# 2_cyber60-mx-matrix.net
KiCad netlist of a schematic drawn in Altium Designer
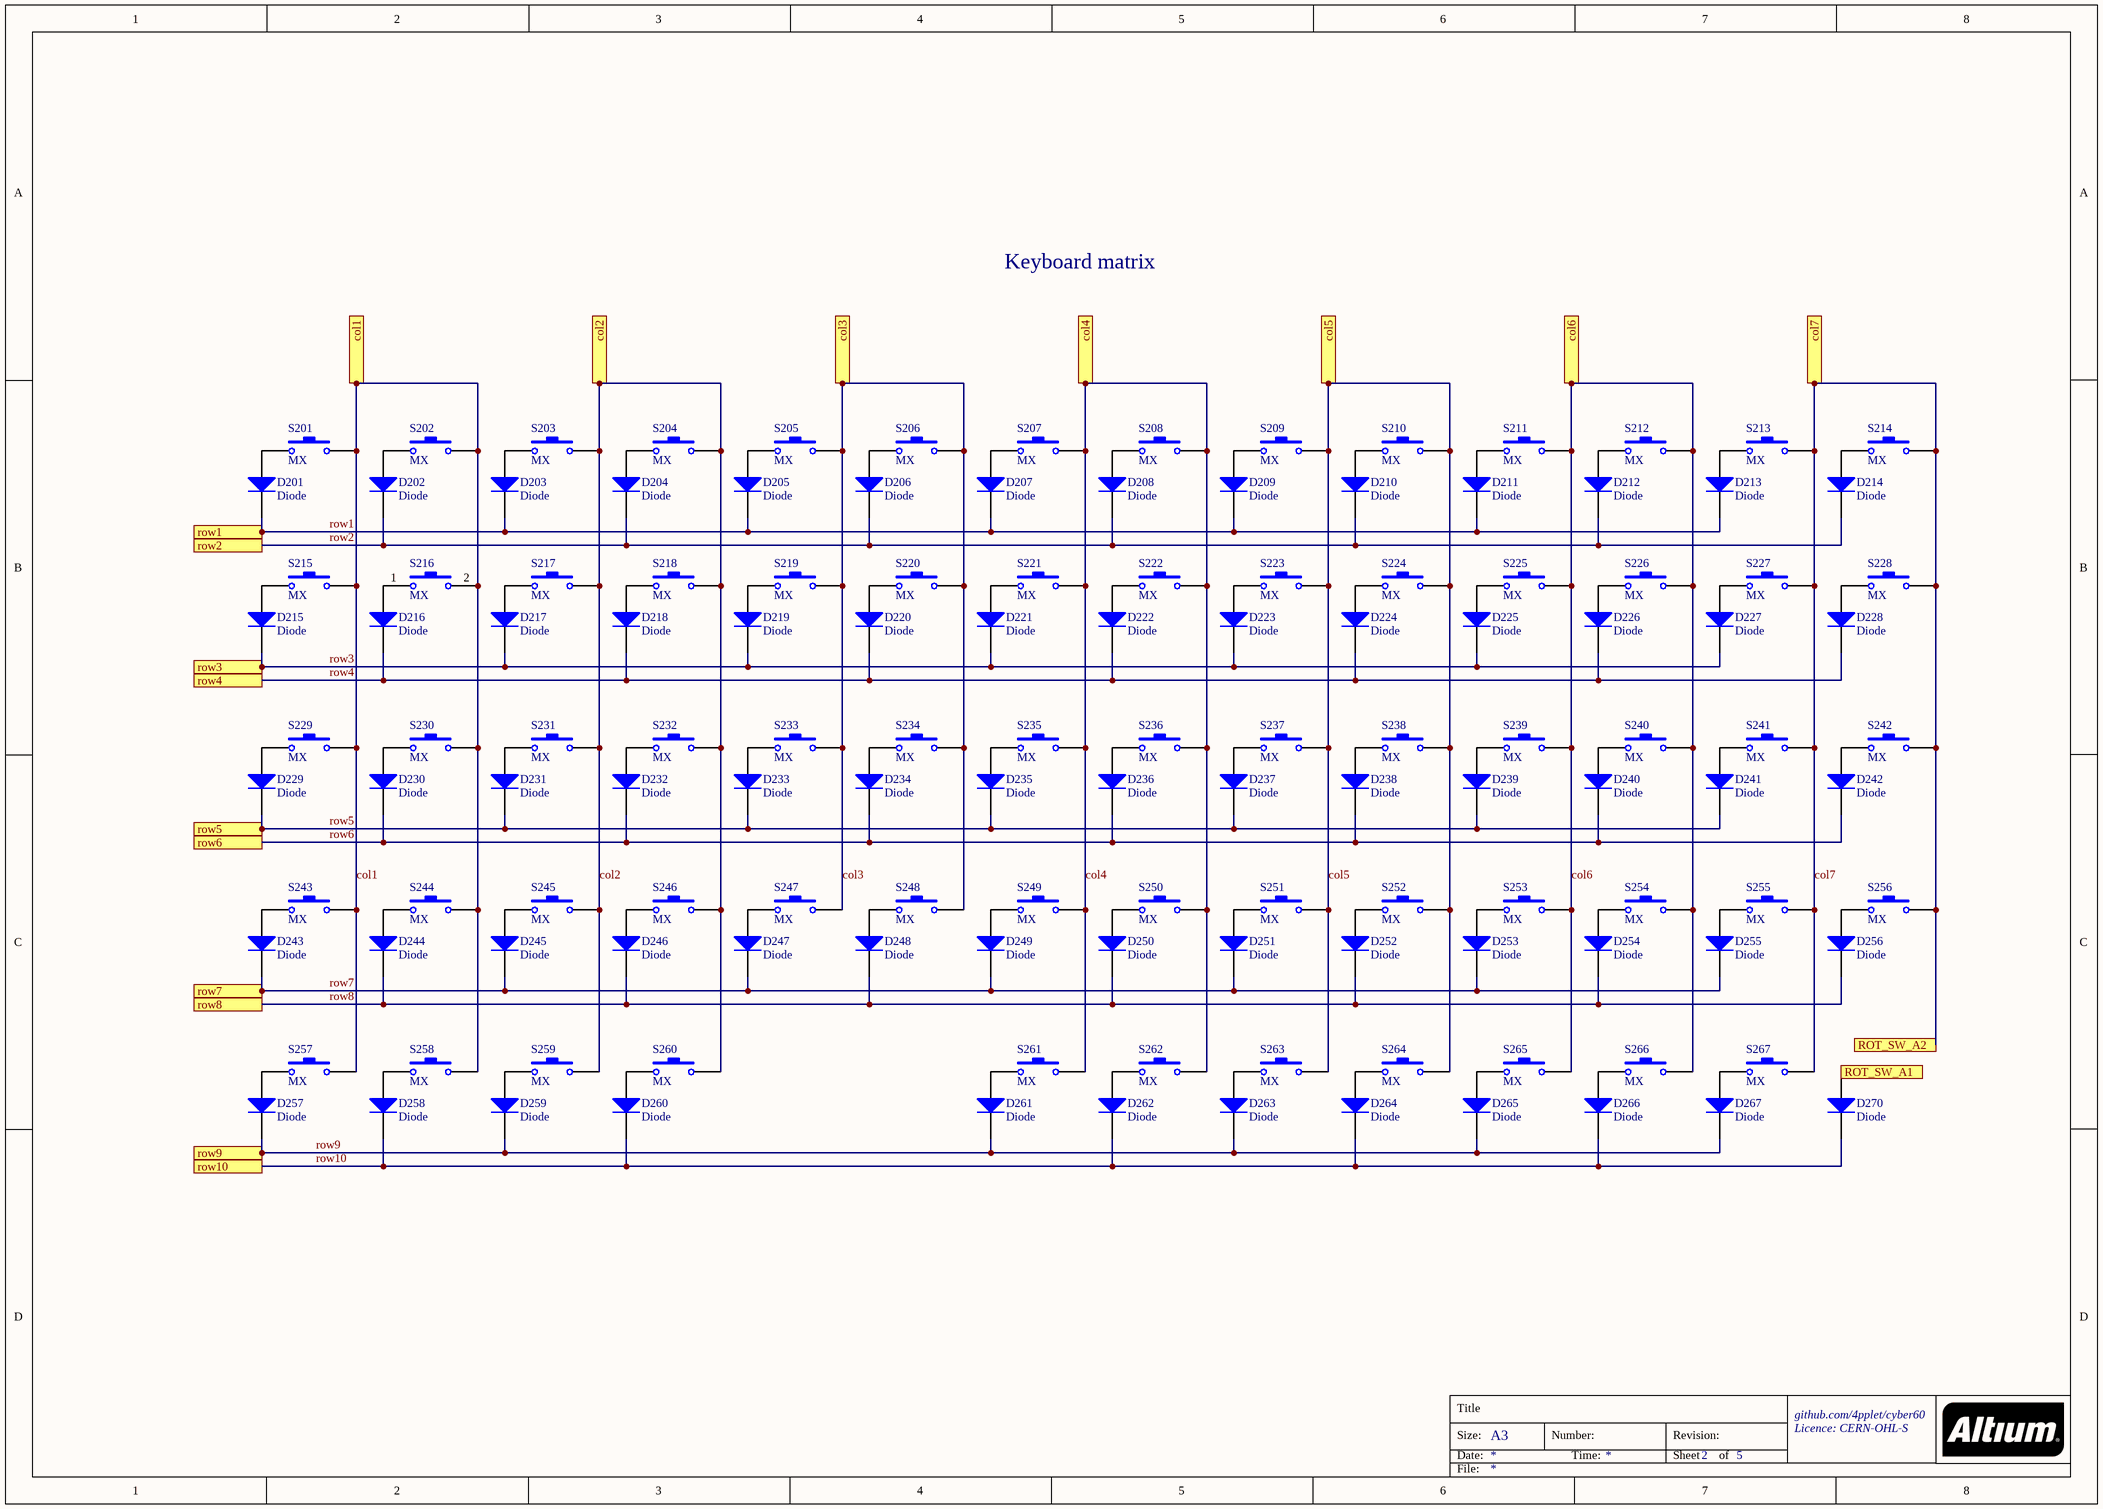
[diagram p0: 2_cyber60-mx-matrix.SchDoc]

(export (version "E")
  (design (tool "Eeschema 10.0.6"))
  (components
    (comp (ref "D201")
      (value "Diode")
      (footprint "SOD-123")
      (description "Default Diode")
      (fields (field (name "LCSC PART #") "C81598") (field (name "MRF.PART") "1N4148W"))
      (libsource (lib "Miscellaneous Devices") (part "Diode"))
    )
    (comp (ref "D202")
      (value "Diode")
      (footprint "SOD-123")
      (description "Default Diode")
      (fields (field (name "LCSC PART #") "C81598") (field (name "MRF.PART") "1N4148W"))
      (libsource (lib "Miscellaneous Devices") (part "Diode"))
    )
    (comp (ref "D203")
      (value "Diode")
      (footprint "SOD-123")
      (description "Default Diode")
      (fields (field (name "LCSC PART #") "C81598") (field (name "MRF.PART") "1N4148W"))
      (libsource (lib "Miscellaneous Devices") (part "Diode"))
    )
    (comp (ref "D204")
      (value "Diode")
      (footprint "SOD-123")
      (description "Default Diode")
      (fields (field (name "LCSC PART #") "C81598") (field (name "MRF.PART") "1N4148W"))
      (libsource (lib "Miscellaneous Devices") (part "Diode"))
    )
    (comp (ref "D205")
      (value "Diode")
      (footprint "SOD-123")
      (description "Default Diode")
      (fields (field (name "LCSC PART #") "C81598") (field (name "MRF.PART") "1N4148W"))
      (libsource (lib "Miscellaneous Devices") (part "Diode"))
    )
    (comp (ref "D206")
      (value "Diode")
      (footprint "SOD-123")
      (description "Default Diode")
      (fields (field (name "LCSC PART #") "C81598") (field (name "MRF.PART") "1N4148W"))
      (libsource (lib "Miscellaneous Devices") (part "Diode"))
    )
    (comp (ref "D207")
      (value "Diode")
      (footprint "SOD-123")
      (description "Default Diode")
      (fields (field (name "LCSC PART #") "C81598") (field (name "MRF.PART") "1N4148W"))
      (libsource (lib "Miscellaneous Devices") (part "Diode"))
    )
    (comp (ref "D208")
      (value "Diode")
      (footprint "SOD-123")
      (description "Default Diode")
      (fields (field (name "LCSC PART #") "C81598") (field (name "MRF.PART") "1N4148W"))
      (libsource (lib "Miscellaneous Devices") (part "Diode"))
    )
    (comp (ref "D209")
      (value "Diode")
      (footprint "SOD-123")
      (description "Default Diode")
      (fields (field (name "LCSC PART #") "C81598") (field (name "MRF.PART") "1N4148W"))
      (libsource (lib "Miscellaneous Devices") (part "Diode"))
    )
    (comp (ref "D210")
      (value "Diode")
      (footprint "SOD-123")
      (description "Default Diode")
      (fields (field (name "LCSC PART #") "C81598") (field (name "MRF.PART") "1N4148W"))
      (libsource (lib "Miscellaneous Devices") (part "Diode"))
    )
    (comp (ref "D211")
      (value "Diode")
      (footprint "SOD-123")
      (description "Default Diode")
      (fields (field (name "LCSC PART #") "C81598") (field (name "MRF.PART") "1N4148W"))
      (libsource (lib "Miscellaneous Devices") (part "Diode"))
    )
    (comp (ref "D212")
      (value "Diode")
      (footprint "SOD-123")
      (description "Default Diode")
      (fields (field (name "LCSC PART #") "C81598") (field (name "MRF.PART") "1N4148W"))
      (libsource (lib "Miscellaneous Devices") (part "Diode"))
    )
    (comp (ref "D213")
      (value "Diode")
      (footprint "SOD-123")
      (description "Default Diode")
      (fields (field (name "LCSC PART #") "C81598") (field (name "MRF.PART") "1N4148W"))
      (libsource (lib "Miscellaneous Devices") (part "Diode"))
    )
    (comp (ref "D214")
      (value "Diode")
      (footprint "SOD-123")
      (description "Default Diode")
      (fields (field (name "LCSC PART #") "C81598") (field (name "MRF.PART") "1N4148W"))
      (libsource (lib "Miscellaneous Devices") (part "Diode"))
    )
    (comp (ref "D215")
      (value "Diode")
      (footprint "SOD-123")
      (description "Default Diode")
      (fields (field (name "LCSC PART #") "C81598") (field (name "MRF.PART") "1N4148W"))
      (libsource (lib "Miscellaneous Devices") (part "Diode"))
    )
    (comp (ref "D216")
      (value "Diode")
      (footprint "SOD-123")
      (description "Default Diode")
      (fields (field (name "LCSC PART #") "C81598") (field (name "MRF.PART") "1N4148W"))
      (libsource (lib "Miscellaneous Devices") (part "Diode"))
    )
    (comp (ref "D217")
      (value "Diode")
      (footprint "SOD-123")
      (description "Default Diode")
      (fields (field (name "LCSC PART #") "C81598") (field (name "MRF.PART") "1N4148W"))
      (libsource (lib "Miscellaneous Devices") (part "Diode"))
    )
    (comp (ref "D218")
      (value "Diode")
      (footprint "SOD-123")
      (description "Default Diode")
      (fields (field (name "LCSC PART #") "C81598") (field (name "MRF.PART") "1N4148W"))
      (libsource (lib "Miscellaneous Devices") (part "Diode"))
    )
    (comp (ref "D219")
      (value "Diode")
      (footprint "SOD-123")
      (description "Default Diode")
      (fields (field (name "LCSC PART #") "C81598") (field (name "MRF.PART") "1N4148W"))
      (libsource (lib "Miscellaneous Devices") (part "Diode"))
    )
    (comp (ref "D220")
      (value "Diode")
      (footprint "SOD-123")
      (description "Default Diode")
      (fields (field (name "LCSC PART #") "C81598") (field (name "MRF.PART") "1N4148W"))
      (libsource (lib "Miscellaneous Devices") (part "Diode"))
    )
    (comp (ref "D221")
      (value "Diode")
      (footprint "SOD-123")
      (description "Default Diode")
      (fields (field (name "LCSC PART #") "C81598") (field (name "MRF.PART") "1N4148W"))
      (libsource (lib "Miscellaneous Devices") (part "Diode"))
    )
    (comp (ref "D222")
      (value "Diode")
      (footprint "SOD-123")
      (description "Default Diode")
      (fields (field (name "LCSC PART #") "C81598") (field (name "MRF.PART") "1N4148W"))
      (libsource (lib "Miscellaneous Devices") (part "Diode"))
    )
    (comp (ref "D223")
      (value "Diode")
      (footprint "SOD-123")
      (description "Default Diode")
      (fields (field (name "LCSC PART #") "C81598") (field (name "MRF.PART") "1N4148W"))
      (libsource (lib "Miscellaneous Devices") (part "Diode"))
    )
    (comp (ref "D224")
      (value "Diode")
      (footprint "SOD-123")
      (description "Default Diode")
      (fields (field (name "LCSC PART #") "C81598") (field (name "MRF.PART") "1N4148W"))
      (libsource (lib "Miscellaneous Devices") (part "Diode"))
    )
    (comp (ref "D225")
      (value "Diode")
      (footprint "SOD-123")
      (description "Default Diode")
      (fields (field (name "LCSC PART #") "C81598") (field (name "MRF.PART") "1N4148W"))
      (libsource (lib "Miscellaneous Devices") (part "Diode"))
    )
    (comp (ref "D226")
      (value "Diode")
      (footprint "SOD-123")
      (description "Default Diode")
      (fields (field (name "LCSC PART #") "C81598") (field (name "MRF.PART") "1N4148W"))
      (libsource (lib "Miscellaneous Devices") (part "Diode"))
    )
    (comp (ref "D227")
      (value "Diode")
      (footprint "SOD-123")
      (description "Default Diode")
      (fields (field (name "LCSC PART #") "C81598") (field (name "MRF.PART") "1N4148W"))
      (libsource (lib "Miscellaneous Devices") (part "Diode"))
    )
    (comp (ref "D228")
      (value "Diode")
      (footprint "SOD-123")
      (description "Default Diode")
      (fields (field (name "LCSC PART #") "C81598") (field (name "MRF.PART") "1N4148W"))
      (libsource (lib "Miscellaneous Devices") (part "Diode"))
    )
    (comp (ref "D229")
      (value "Diode")
      (footprint "SOD-123")
      (description "Default Diode")
      (fields (field (name "LCSC PART #") "C81598") (field (name "MRF.PART") "1N4148W"))
      (libsource (lib "Miscellaneous Devices") (part "Diode"))
    )
    (comp (ref "D230")
      (value "Diode")
      (footprint "SOD-123")
      (description "Default Diode")
      (fields (field (name "LCSC PART #") "C81598") (field (name "MRF.PART") "1N4148W"))
      (libsource (lib "Miscellaneous Devices") (part "Diode"))
    )
    (comp (ref "D231")
      (value "Diode")
      (footprint "SOD-123")
      (description "Default Diode")
      (fields (field (name "LCSC PART #") "C81598") (field (name "MRF.PART") "1N4148W"))
      (libsource (lib "Miscellaneous Devices") (part "Diode"))
    )
    (comp (ref "D232")
      (value "Diode")
      (footprint "SOD-123")
      (description "Default Diode")
      (fields (field (name "LCSC PART #") "C81598") (field (name "MRF.PART") "1N4148W"))
      (libsource (lib "Miscellaneous Devices") (part "Diode"))
    )
    (comp (ref "D233")
      (value "Diode")
      (footprint "SOD-123")
      (description "Default Diode")
      (fields (field (name "LCSC PART #") "C81598") (field (name "MRF.PART") "1N4148W"))
      (libsource (lib "Miscellaneous Devices") (part "Diode"))
    )
    (comp (ref "D234")
      (value "Diode")
      (footprint "SOD-123")
      (description "Default Diode")
      (fields (field (name "LCSC PART #") "C81598") (field (name "MRF.PART") "1N4148W"))
      (libsource (lib "Miscellaneous Devices") (part "Diode"))
    )
    (comp (ref "D235")
      (value "Diode")
      (footprint "SOD-123")
      (description "Default Diode")
      (fields (field (name "LCSC PART #") "C81598") (field (name "MRF.PART") "1N4148W"))
      (libsource (lib "Miscellaneous Devices") (part "Diode"))
    )
    (comp (ref "D236")
      (value "Diode")
      (footprint "SOD-123")
      (description "Default Diode")
      (fields (field (name "LCSC PART #") "C81598") (field (name "MRF.PART") "1N4148W"))
      (libsource (lib "Miscellaneous Devices") (part "Diode"))
    )
    (comp (ref "D237")
      (value "Diode")
      (footprint "SOD-123")
      (description "Default Diode")
      (fields (field (name "LCSC PART #") "C81598") (field (name "MRF.PART") "1N4148W"))
      (libsource (lib "Miscellaneous Devices") (part "Diode"))
    )
    (comp (ref "D238")
      (value "Diode")
      (footprint "SOD-123")
      (description "Default Diode")
      (fields (field (name "LCSC PART #") "C81598") (field (name "MRF.PART") "1N4148W"))
      (libsource (lib "Miscellaneous Devices") (part "Diode"))
    )
    (comp (ref "D239")
      (value "Diode")
      (footprint "SOD-123")
      (description "Default Diode")
      (fields (field (name "LCSC PART #") "C81598") (field (name "MRF.PART") "1N4148W"))
      (libsource (lib "Miscellaneous Devices") (part "Diode"))
    )
    (comp (ref "D240")
      (value "Diode")
      (footprint "SOD-123")
      (description "Default Diode")
      (fields (field (name "LCSC PART #") "C81598") (field (name "MRF.PART") "1N4148W"))
      (libsource (lib "Miscellaneous Devices") (part "Diode"))
    )
    (comp (ref "D241")
      (value "Diode")
      (footprint "SOD-123")
      (description "Default Diode")
      (fields (field (name "LCSC PART #") "C81598") (field (name "MRF.PART") "1N4148W"))
      (libsource (lib "Miscellaneous Devices") (part "Diode"))
    )
    (comp (ref "D242")
      (value "Diode")
      (footprint "SOD-123")
      (description "Default Diode")
      (fields (field (name "LCSC PART #") "C81598") (field (name "MRF.PART") "1N4148W"))
      (libsource (lib "Miscellaneous Devices") (part "Diode"))
    )
    (comp (ref "D243")
      (value "Diode")
      (footprint "SOD-123")
      (description "Default Diode")
      (fields (field (name "LCSC PART #") "C81598") (field (name "MRF.PART") "1N4148W"))
      (libsource (lib "Miscellaneous Devices") (part "Diode"))
    )
    (comp (ref "D244")
      (value "Diode")
      (footprint "SOD-123")
      (description "Default Diode")
      (fields (field (name "LCSC PART #") "C81598") (field (name "MRF.PART") "1N4148W"))
      (libsource (lib "Miscellaneous Devices") (part "Diode"))
    )
    (comp (ref "D245")
      (value "Diode")
      (footprint "SOD-123")
      (description "Default Diode")
      (fields (field (name "LCSC PART #") "C81598") (field (name "MRF.PART") "1N4148W"))
      (libsource (lib "Miscellaneous Devices") (part "Diode"))
    )
    (comp (ref "D246")
      (value "Diode")
      (footprint "SOD-123")
      (description "Default Diode")
      (fields (field (name "LCSC PART #") "C81598") (field (name "MRF.PART") "1N4148W"))
      (libsource (lib "Miscellaneous Devices") (part "Diode"))
    )
    (comp (ref "D247")
      (value "Diode")
      (footprint "SOD-123")
      (description "Default Diode")
      (fields (field (name "LCSC PART #") "C81598") (field (name "MRF.PART") "1N4148W"))
      (libsource (lib "Miscellaneous Devices") (part "Diode"))
    )
    (comp (ref "D248")
      (value "Diode")
      (footprint "SOD-123")
      (description "Default Diode")
      (fields (field (name "LCSC PART #") "C81598") (field (name "MRF.PART") "1N4148W"))
      (libsource (lib "Miscellaneous Devices") (part "Diode"))
    )
    (comp (ref "D249")
      (value "Diode")
      (footprint "SOD-123")
      (description "Default Diode")
      (fields (field (name "LCSC PART #") "C81598") (field (name "MRF.PART") "1N4148W"))
      (libsource (lib "Miscellaneous Devices") (part "Diode"))
    )
    (comp (ref "D250")
      (value "Diode")
      (footprint "SOD-123")
      (description "Default Diode")
      (fields (field (name "LCSC PART #") "C81598") (field (name "MRF.PART") "1N4148W"))
      (libsource (lib "Miscellaneous Devices") (part "Diode"))
    )
    (comp (ref "D251")
      (value "Diode")
      (footprint "SOD-123")
      (description "Default Diode")
      (fields (field (name "LCSC PART #") "C81598") (field (name "MRF.PART") "1N4148W"))
      (libsource (lib "Miscellaneous Devices") (part "Diode"))
    )
    (comp (ref "D252")
      (value "Diode")
      (footprint "SOD-123")
      (description "Default Diode")
      (fields (field (name "LCSC PART #") "C81598") (field (name "MRF.PART") "1N4148W"))
      (libsource (lib "Miscellaneous Devices") (part "Diode"))
    )
    (comp (ref "D253")
      (value "Diode")
      (footprint "SOD-123")
      (description "Default Diode")
      (fields (field (name "LCSC PART #") "C81598") (field (name "MRF.PART") "1N4148W"))
      (libsource (lib "Miscellaneous Devices") (part "Diode"))
    )
    (comp (ref "D254")
      (value "Diode")
      (footprint "SOD-123")
      (description "Default Diode")
      (fields (field (name "LCSC PART #") "C81598") (field (name "MRF.PART") "1N4148W"))
      (libsource (lib "Miscellaneous Devices") (part "Diode"))
    )
    (comp (ref "D255")
      (value "Diode")
      (footprint "SOD-123")
      (description "Default Diode")
      (fields (field (name "LCSC PART #") "C81598") (field (name "MRF.PART") "1N4148W"))
      (libsource (lib "Miscellaneous Devices") (part "Diode"))
    )
    (comp (ref "D256")
      (value "Diode")
      (footprint "SOD-123")
      (description "Default Diode")
      (fields (field (name "LCSC PART #") "C81598") (field (name "MRF.PART") "1N4148W"))
      (libsource (lib "Miscellaneous Devices") (part "Diode"))
    )
    (comp (ref "D257")
      (value "Diode")
      (footprint "SOD-123")
      (description "Default Diode")
      (fields (field (name "LCSC PART #") "C81598") (field (name "MRF.PART") "1N4148W"))
      (libsource (lib "Miscellaneous Devices") (part "Diode"))
    )
    (comp (ref "D258")
      (value "Diode")
      (footprint "SOD-123")
      (description "Default Diode")
      (fields (field (name "LCSC PART #") "C81598") (field (name "MRF.PART") "1N4148W"))
      (libsource (lib "Miscellaneous Devices") (part "Diode"))
    )
    (comp (ref "D259")
      (value "Diode")
      (footprint "SOD-123")
      (description "Default Diode")
      (fields (field (name "LCSC PART #") "C81598") (field (name "MRF.PART") "1N4148W"))
      (libsource (lib "Miscellaneous Devices") (part "Diode"))
    )
    (comp (ref "D260")
      (value "Diode")
      (footprint "SOD-123")
      (description "Default Diode")
      (fields (field (name "LCSC PART #") "C81598") (field (name "MRF.PART") "1N4148W"))
      (libsource (lib "Miscellaneous Devices") (part "Diode"))
    )
    (comp (ref "D261")
      (value "Diode")
      (footprint "SOD-123")
      (description "Default Diode")
      (fields (field (name "LCSC PART #") "C81598") (field (name "MRF.PART") "1N4148W"))
      (libsource (lib "Miscellaneous Devices") (part "Diode"))
    )
    (comp (ref "D262")
      (value "Diode")
      (footprint "SOD-123")
      (description "Default Diode")
      (fields (field (name "LCSC PART #") "C81598") (field (name "MRF.PART") "1N4148W"))
      (libsource (lib "Miscellaneous Devices") (part "Diode"))
    )
    (comp (ref "D263")
      (value "Diode")
      (footprint "SOD-123")
      (description "Default Diode")
      (fields (field (name "LCSC PART #") "C81598") (field (name "MRF.PART") "1N4148W"))
      (libsource (lib "Miscellaneous Devices") (part "Diode"))
    )
    (comp (ref "D264")
      (value "Diode")
      (footprint "SOD-123")
      (description "Default Diode")
      (fields (field (name "LCSC PART #") "C81598") (field (name "MRF.PART") "1N4148W"))
      (libsource (lib "Miscellaneous Devices") (part "Diode"))
    )
    (comp (ref "D265")
      (value "Diode")
      (footprint "SOD-123")
      (description "Default Diode")
      (fields (field (name "LCSC PART #") "C81598") (field (name "MRF.PART") "1N4148W"))
      (libsource (lib "Miscellaneous Devices") (part "Diode"))
    )
    (comp (ref "D266")
      (value "Diode")
      (footprint "SOD-123")
      (description "Default Diode")
      (fields (field (name "LCSC PART #") "C81598") (field (name "MRF.PART") "1N4148W"))
      (libsource (lib "Miscellaneous Devices") (part "Diode"))
    )
    (comp (ref "D267")
      (value "Diode")
      (footprint "SOD-123")
      (description "Default Diode")
      (fields (field (name "LCSC PART #") "C81598") (field (name "MRF.PART") "1N4148W"))
      (libsource (lib "Miscellaneous Devices") (part "Diode"))
    )
    (comp (ref "D270")
      (value "Diode")
      (footprint "SOD-123")
      (description "Default Diode")
      (fields (field (name "LCSC PART #") "C81598") (field (name "MRF.PART") "1N4148W"))
      (libsource (lib "Miscellaneous Devices") (part "Diode"))
    )
    (comp (ref "S201")
      (value "MX")
      (footprint "MX-switch - switched pol")
      (description "Switch")
      (libsource (lib "Miscellaneous Devices") (part "SW-PB"))
    )
    (comp (ref "S202")
      (value "MX")
      (footprint "MX-switch - switched pol - connector")
      (description "Switch")
      (libsource (lib "Miscellaneous Devices") (part "SW-PB"))
    )
    (comp (ref "S203")
      (value "MX")
      (footprint "MX-switch - switched pol")
      (description "Switch")
      (libsource (lib "Miscellaneous Devices") (part "SW-PB"))
    )
    (comp (ref "S204")
      (value "MX")
      (footprint "MX-switch")
      (description "Switch")
      (libsource (lib "Miscellaneous Devices") (part "SW-PB"))
    )
    (comp (ref "S205")
      (value "MX")
      (footprint "MX-switch - switched pol")
      (description "Switch")
      (libsource (lib "Miscellaneous Devices") (part "SW-PB"))
    )
    (comp (ref "S206")
      (value "MX")
      (footprint "MX-switch - switched pol")
      (description "Switch")
      (libsource (lib "Miscellaneous Devices") (part "SW-PB"))
    )
    (comp (ref "S207")
      (value "MX")
      (footprint "MX-switch - switched pol")
      (description "Switch")
      (libsource (lib "Miscellaneous Devices") (part "SW-PB"))
    )
    (comp (ref "S208")
      (value "MX")
      (footprint "MX-switch - switched pol")
      (description "Switch")
      (libsource (lib "Miscellaneous Devices") (part "SW-PB"))
    )
    (comp (ref "S209")
      (value "MX")
      (footprint "MX-switch - switched pol")
      (description "Switch")
      (libsource (lib "Miscellaneous Devices") (part "SW-PB"))
    )
    (comp (ref "S210")
      (value "MX")
      (footprint "MX-switch - switched pol")
      (description "Switch")
      (libsource (lib "Miscellaneous Devices") (part "SW-PB"))
    )
    (comp (ref "S211")
      (value "MX")
      (footprint "MX-switch - switched pol")
      (description "Switch")
      (libsource (lib "Miscellaneous Devices") (part "SW-PB"))
    )
    (comp (ref "S212")
      (value "MX")
      (footprint "MX-switch - switched pol")
      (description "Switch")
      (libsource (lib "Miscellaneous Devices") (part "SW-PB"))
    )
    (comp (ref "S213")
      (value "MX")
      (footprint "MX-switch - switched pol")
      (description "Switch")
      (libsource (lib "Miscellaneous Devices") (part "SW-PB"))
    )
    (comp (ref "S214")
      (value "MX")
      (footprint "MX-switch - switched pol")
      (description "Switch")
      (libsource (lib "Miscellaneous Devices") (part "SW-PB"))
    )
    (comp (ref "S215")
      (value "MX")
      (footprint "MX-switch - 1.5U - switched pol")
      (description "TAB")
      (libsource (lib "Miscellaneous Devices") (part "SW-PB"))
    )
    (comp (ref "S216")
      (value "MX")
      (footprint "MX-switch - switched pol")
      (description "Switch")
      (libsource (lib "") (part "SW-PB_1"))
    )
    (comp (ref "S217")
      (value "MX")
      (footprint "MX-switch - switched pol")
      (description "Switch")
      (libsource (lib "Miscellaneous Devices") (part "SW-PB"))
    )
    (comp (ref "S218")
      (value "MX")
      (footprint "MX-switch - switched pol")
      (description "Switch")
      (libsource (lib "Miscellaneous Devices") (part "SW-PB"))
    )
    (comp (ref "S219")
      (value "MX")
      (footprint "MX-switch - switched pol")
      (description "Switch")
      (libsource (lib "Miscellaneous Devices") (part "SW-PB"))
    )
    (comp (ref "S220")
      (value "MX")
      (footprint "MX-switch")
      (description "Switch")
      (libsource (lib "Miscellaneous Devices") (part "SW-PB"))
    )
    (comp (ref "S221")
      (value "MX")
      (footprint "MX-switch - switched pol")
      (description "Switch")
      (libsource (lib "Miscellaneous Devices") (part "SW-PB"))
    )
    (comp (ref "S222")
      (value "MX")
      (footprint "MX-switch - switched pol")
      (description "Switch")
      (libsource (lib "Miscellaneous Devices") (part "SW-PB"))
    )
    (comp (ref "S223")
      (value "MX")
      (footprint "MX-switch - switched pol")
      (description "Switch")
      (libsource (lib "Miscellaneous Devices") (part "SW-PB"))
    )
    (comp (ref "S224")
      (value "MX")
      (footprint "MX-switch - switched pol")
      (description "Switch")
      (libsource (lib "Miscellaneous Devices") (part "SW-PB"))
    )
    (comp (ref "S225")
      (value "MX")
      (footprint "MX-switch - switched pol")
      (description "Switch")
      (libsource (lib "Miscellaneous Devices") (part "SW-PB"))
    )
    (comp (ref "S226")
      (value "MX")
      (footprint "MX-switch")
      (description "Switch")
      (libsource (lib "Miscellaneous Devices") (part "SW-PB"))
    )
    (comp (ref "S227")
      (value "MX")
      (footprint "MX-switch")
      (description "Switch")
      (libsource (lib "Miscellaneous Devices") (part "SW-PB"))
    )
    (comp (ref "S228")
      (value "MX")
      (footprint "MX-switch - backspace")
      (description "Switch")
      (libsource (lib "Miscellaneous Devices") (part "SW-PB"))
    )
    (comp (ref "S229")
      (value "MX")
      (footprint "MX-switch - CAPS")
      (description "Switch")
      (libsource (lib "Miscellaneous Devices") (part "SW-PB"))
    )
    (comp (ref "S230")
      (value "MX")
      (footprint "MX-switch - switched pol")
      (description "Switch")
      (libsource (lib "Miscellaneous Devices") (part "SW-PB"))
    )
    (comp (ref "S231")
      (value "MX")
      (footprint "MX-switch - switched pol")
      (description "Switch")
      (libsource (lib "Miscellaneous Devices") (part "SW-PB"))
    )
    (comp (ref "S232")
      (value "MX")
      (footprint "MX-switch - switched pol")
      (description "Switch")
      (libsource (lib "Miscellaneous Devices") (part "SW-PB"))
    )
    (comp (ref "S233")
      (value "MX")
      (footprint "MX-switch - switched pol")
      (description "Switch")
      (libsource (lib "Miscellaneous Devices") (part "SW-PB"))
    )
    (comp (ref "S234")
      (value "MX")
      (footprint "MX-switch")
      (description "Switch")
      (libsource (lib "Miscellaneous Devices") (part "SW-PB"))
    )
    (comp (ref "S235")
      (value "MX")
      (footprint "MX-switch - switched pol")
      (description "Switch")
      (libsource (lib "Miscellaneous Devices") (part "SW-PB"))
    )
    (comp (ref "S236")
      (value "MX")
      (footprint "MX-switch - switched pol")
      (description "Switch")
      (libsource (lib "Miscellaneous Devices") (part "SW-PB"))
    )
    (comp (ref "S237")
      (value "MX")
      (footprint "MX-switch - switched pol")
      (description "Switch")
      (libsource (lib "Miscellaneous Devices") (part "SW-PB"))
    )
    (comp (ref "S238")
      (value "MX")
      (footprint "MX-switch - switched pol")
      (description "Switch")
      (libsource (lib "Miscellaneous Devices") (part "SW-PB"))
    )
    (comp (ref "S239")
      (value "MX")
      (footprint "MX-switch")
      (description "Switch")
      (libsource (lib "Miscellaneous Devices") (part "SW-PB"))
    )
    (comp (ref "S240")
      (value "MX")
      (footprint "MX-switch - switched pol")
      (description "Switch")
      (libsource (lib "Miscellaneous Devices") (part "SW-PB"))
    )
    (comp (ref "S241")
      (value "MX")
      (footprint "MX-switch")
      (description "Switch")
      (libsource (lib "Miscellaneous Devices") (part "SW-PB"))
    )
    (comp (ref "S242")
      (value "MX")
      (footprint "MX-switch - 1.5U")
      (description "Switch")
      (libsource (lib "Miscellaneous Devices") (part "SW-PB"))
    )
    (comp (ref "S243")
      (value "MX")
      (footprint "MX-switch - Left shift")
      (description "Switch")
      (libsource (lib "Miscellaneous Devices") (part "SW-PB"))
    )
    (comp (ref "S244")
      (value "MX")
      (footprint "MX-switch - switched pol")
      (description "Switch")
      (libsource (lib "Miscellaneous Devices") (part "SW-PB"))
    )
    (comp (ref "S245")
      (value "MX")
      (footprint "MX-switch - switched pol")
      (description "Switch")
      (libsource (lib "Miscellaneous Devices") (part "SW-PB"))
    )
    (comp (ref "S246")
      (value "MX")
      (footprint "MX-switch - switched pol")
      (description "Switch")
      (libsource (lib "Miscellaneous Devices") (part "SW-PB"))
    )
    (comp (ref "S247")
      (value "MX")
      (footprint "MX-switch - switched pol")
      (description "Switch")
      (libsource (lib "Miscellaneous Devices") (part "SW-PB"))
    )
    (comp (ref "S248")
      (value "MX")
      (footprint "MX-switch")
      (description "Switch")
      (libsource (lib "Miscellaneous Devices") (part "SW-PB"))
    )
    (comp (ref "S249")
      (value "MX")
      (footprint "MX-switch - switched pol")
      (description "Switch")
      (libsource (lib "Miscellaneous Devices") (part "SW-PB"))
    )
    (comp (ref "S250")
      (value "MX")
      (footprint "MX-switch - switched pol")
      (description "Switch")
      (libsource (lib "Miscellaneous Devices") (part "SW-PB"))
    )
    (comp (ref "S251")
      (value "MX")
      (footprint "MX-switch - switched pol")
      (description "Switch")
      (libsource (lib "Miscellaneous Devices") (part "SW-PB"))
    )
    (comp (ref "S252")
      (value "MX")
      (footprint "MX-switch - switched pol")
      (description "Switch")
      (libsource (lib "Miscellaneous Devices") (part "SW-PB"))
    )
    (comp (ref "S253")
      (value "MX")
      (footprint "MX-switch - switched pol")
      (description "Switch")
      (libsource (lib "Miscellaneous Devices") (part "SW-PB"))
    )
    (comp (ref "S254")
      (value "MX")
      (footprint "MX-switch - switched pol")
      (description "Switch")
      (libsource (lib "Miscellaneous Devices") (part "SW-PB"))
    )
    (comp (ref "S255")
      (value "MX")
      (footprint "MX-switch")
      (description "Switch")
      (libsource (lib "Miscellaneous Devices") (part "SW-PB"))
    )
    (comp (ref "S256")
      (value "MX")
      (footprint "MX-switch - Enter - Rotated Stab")
      (description "Switch")
      (libsource (lib "Miscellaneous Devices") (part "SW-PB"))
    )
    (comp (ref "S257")
      (value "MX")
      (footprint "MX-switch - 1.5u MOD-L")
      (description "Switch")
      (libsource (lib "Miscellaneous Devices") (part "SW-PB"))
    )
    (comp (ref "S258")
      (value "MX")
      (footprint "MX-switch - 1u MOD-L")
      (description "Switch")
      (libsource (lib "Miscellaneous Devices") (part "SW-PB"))
    )
    (comp (ref "S259")
      (value "MX")
      (footprint "MX-switch - 1.5u MOD-L")
      (description "Switch")
      (libsource (lib "Miscellaneous Devices") (part "SW-PB"))
    )
    (comp (ref "S260")
      (value "MX")
      (footprint "MX-switch - 3U - rotated stab")
      (description "Switch")
      (libsource (lib "Miscellaneous Devices") (part "SW-PB"))
    )
    (comp (ref "S261")
      (value "MX")
      (footprint "MX-switch - Space_V2")
      (description "Switch")
      (libsource (lib "Miscellaneous Devices") (part "SW-PB"))
    )
    (comp (ref "S262")
      (value "MX")
      (footprint "MX-switch - 3U - rotated stab")
      (description "Switch")
      (libsource (lib "Miscellaneous Devices") (part "SW-PB"))
    )
    (comp (ref "S263")
      (value "MX")
      (footprint "MX-switch - switched pol")
      (description "Switch")
      (libsource (lib "Miscellaneous Devices") (part "SW-PB"))
    )
    (comp (ref "S264")
      (value "MX")
      (footprint "MX-switch - 1.5u MOD-R")
      (description "Switch")
      (libsource (lib "Miscellaneous Devices") (part "SW-PB"))
    )
    (comp (ref "S265")
      (value "MX")
      (footprint "MX-switch - 1u MOD-R")
      (description "Switch")
      (libsource (lib "Miscellaneous Devices") (part "SW-PB"))
    )
    (comp (ref "S266")
      (value "MX")
      (footprint "MX-switch - 1.5u MOD-R")
      (description "Switch")
      (libsource (lib "Miscellaneous Devices") (part "SW-PB"))
    )
    (comp (ref "S267")
      (value "MX")
      (footprint "MX-switch - right shift")
      (description "Switch")
      (libsource (lib "Miscellaneous Devices") (part "SW-PB"))
    )
  )
  (nets
    (net (code "1") (name "/ROT_SW_A1") (class "Default")
      (node (ref "D270") (pin "1") (pinfunction "A_1") (pintype "passive"))
    )
    (net (code "2") (name "/col1") (class "Default")
      (node (ref "S201") (pin "2") (pinfunction "2_2") (pintype "passive"))
      (node (ref "S202") (pin "2") (pinfunction "2_2") (pintype "passive"))
      (node (ref "S215") (pin "2") (pinfunction "2_2") (pintype "passive"))
      (node (ref "S216") (pin "2") (pinfunction "2_2") (pintype "passive"))
      (node (ref "S229") (pin "2") (pinfunction "2_2") (pintype "passive"))
      (node (ref "S230") (pin "2") (pinfunction "2_2") (pintype "passive"))
      (node (ref "S243") (pin "2") (pinfunction "2_2") (pintype "passive"))
      (node (ref "S244") (pin "2") (pinfunction "2_2") (pintype "passive"))
      (node (ref "S257") (pin "2") (pinfunction "2_2") (pintype "passive"))
      (node (ref "S258") (pin "2") (pinfunction "2_2") (pintype "passive"))
    )
    (net (code "3") (name "/col2") (class "Default")
      (node (ref "S203") (pin "2") (pinfunction "2_2") (pintype "passive"))
      (node (ref "S204") (pin "2") (pinfunction "2_2") (pintype "passive"))
      (node (ref "S217") (pin "2") (pinfunction "2_2") (pintype "passive"))
      (node (ref "S218") (pin "2") (pinfunction "2_2") (pintype "passive"))
      (node (ref "S231") (pin "2") (pinfunction "2_2") (pintype "passive"))
      (node (ref "S232") (pin "2") (pinfunction "2_2") (pintype "passive"))
      (node (ref "S245") (pin "2") (pinfunction "2_2") (pintype "passive"))
      (node (ref "S246") (pin "2") (pinfunction "2_2") (pintype "passive"))
      (node (ref "S259") (pin "2") (pinfunction "2_2") (pintype "passive"))
      (node (ref "S260") (pin "2") (pinfunction "2_2") (pintype "passive"))
    )
    (net (code "4") (name "/col3") (class "Default")
      (node (ref "S205") (pin "2") (pinfunction "2_2") (pintype "passive"))
      (node (ref "S206") (pin "2") (pinfunction "2_2") (pintype "passive"))
      (node (ref "S219") (pin "2") (pinfunction "2_2") (pintype "passive"))
      (node (ref "S220") (pin "2") (pinfunction "2_2") (pintype "passive"))
      (node (ref "S233") (pin "2") (pinfunction "2_2") (pintype "passive"))
      (node (ref "S234") (pin "2") (pinfunction "2_2") (pintype "passive"))
      (node (ref "S247") (pin "2") (pinfunction "2_2") (pintype "passive"))
      (node (ref "S248") (pin "2") (pinfunction "2_2") (pintype "passive"))
    )
    (net (code "5") (name "/col4") (class "Default")
      (node (ref "S207") (pin "2") (pinfunction "2_2") (pintype "passive"))
      (node (ref "S208") (pin "2") (pinfunction "2_2") (pintype "passive"))
      (node (ref "S221") (pin "2") (pinfunction "2_2") (pintype "passive"))
      (node (ref "S222") (pin "2") (pinfunction "2_2") (pintype "passive"))
      (node (ref "S235") (pin "2") (pinfunction "2_2") (pintype "passive"))
      (node (ref "S236") (pin "2") (pinfunction "2_2") (pintype "passive"))
      (node (ref "S249") (pin "2") (pinfunction "2_2") (pintype "passive"))
      (node (ref "S250") (pin "2") (pinfunction "2_2") (pintype "passive"))
      (node (ref "S261") (pin "1") (pinfunction "1_1") (pintype "passive"))
      (node (ref "S262") (pin "2") (pinfunction "2_2") (pintype "passive"))
    )
    (net (code "6") (name "/col5") (class "Default")
      (node (ref "S209") (pin "2") (pinfunction "2_2") (pintype "passive"))
      (node (ref "S210") (pin "2") (pinfunction "2_2") (pintype "passive"))
      (node (ref "S223") (pin "2") (pinfunction "2_2") (pintype "passive"))
      (node (ref "S224") (pin "2") (pinfunction "2_2") (pintype "passive"))
      (node (ref "S237") (pin "2") (pinfunction "2_2") (pintype "passive"))
      (node (ref "S238") (pin "2") (pinfunction "2_2") (pintype "passive"))
      (node (ref "S251") (pin "2") (pinfunction "2_2") (pintype "passive"))
      (node (ref "S252") (pin "2") (pinfunction "2_2") (pintype "passive"))
      (node (ref "S263") (pin "2") (pinfunction "2_2") (pintype "passive"))
      (node (ref "S264") (pin "1") (pinfunction "1_1") (pintype "passive"))
    )
    (net (code "7") (name "/col6") (class "Default")
      (node (ref "S211") (pin "2") (pinfunction "2_2") (pintype "passive"))
      (node (ref "S212") (pin "2") (pinfunction "2_2") (pintype "passive"))
      (node (ref "S225") (pin "2") (pinfunction "2_2") (pintype "passive"))
      (node (ref "S226") (pin "2") (pinfunction "2_2") (pintype "passive"))
      (node (ref "S239") (pin "2") (pinfunction "2_2") (pintype "passive"))
      (node (ref "S240") (pin "2") (pinfunction "2_2") (pintype "passive"))
      (node (ref "S253") (pin "2") (pinfunction "2_2") (pintype "passive"))
      (node (ref "S254") (pin "2") (pinfunction "2_2") (pintype "passive"))
      (node (ref "S265") (pin "2") (pinfunction "2_2") (pintype "passive"))
      (node (ref "S266") (pin "2") (pinfunction "2_2") (pintype "passive"))
    )
    (net (code "8") (name "/col7") (class "Default")
      (node (ref "S213") (pin "2") (pinfunction "2_2") (pintype "passive"))
      (node (ref "S214") (pin "2") (pinfunction "2_2") (pintype "passive"))
      (node (ref "S227") (pin "2") (pinfunction "2_2") (pintype "passive"))
      (node (ref "S228") (pin "1") (pinfunction "1_1") (pintype "passive"))
      (node (ref "S241") (pin "2") (pinfunction "2_2") (pintype "passive"))
      (node (ref "S242") (pin "2") (pinfunction "2_2") (pintype "passive"))
      (node (ref "S255") (pin "2") (pinfunction "2_2") (pintype "passive"))
      (node (ref "S256") (pin "2") (pinfunction "2_2") (pintype "passive"))
      (node (ref "S267") (pin "2") (pinfunction "2_2") (pintype "passive"))
    )
    (net (code "9") (name "/row1") (class "Default")
      (node (ref "D201") (pin "2") (pinfunction "K_2") (pintype "passive"))
      (node (ref "D203") (pin "2") (pinfunction "K_2") (pintype "passive"))
      (node (ref "D205") (pin "2") (pinfunction "K_2") (pintype "passive"))
      (node (ref "D207") (pin "2") (pinfunction "K_2") (pintype "passive"))
      (node (ref "D209") (pin "2") (pinfunction "K_2") (pintype "passive"))
      (node (ref "D211") (pin "2") (pinfunction "K_2") (pintype "passive"))
      (node (ref "D213") (pin "2") (pinfunction "K_2") (pintype "passive"))
    )
    (net (code "10") (name "/row2") (class "Default")
      (node (ref "D202") (pin "2") (pinfunction "K_2") (pintype "passive"))
      (node (ref "D204") (pin "2") (pinfunction "K_2") (pintype "passive"))
      (node (ref "D206") (pin "2") (pinfunction "K_2") (pintype "passive"))
      (node (ref "D208") (pin "2") (pinfunction "K_2") (pintype "passive"))
      (node (ref "D210") (pin "2") (pinfunction "K_2") (pintype "passive"))
      (node (ref "D212") (pin "2") (pinfunction "K_2") (pintype "passive"))
      (node (ref "D214") (pin "2") (pinfunction "K_2") (pintype "passive"))
    )
    (net (code "11") (name "/row3") (class "Default")
      (node (ref "D215") (pin "2") (pinfunction "K_2") (pintype "passive"))
      (node (ref "D217") (pin "2") (pinfunction "K_2") (pintype "passive"))
      (node (ref "D219") (pin "2") (pinfunction "K_2") (pintype "passive"))
      (node (ref "D221") (pin "2") (pinfunction "K_2") (pintype "passive"))
      (node (ref "D223") (pin "2") (pinfunction "K_2") (pintype "passive"))
      (node (ref "D225") (pin "2") (pinfunction "K_2") (pintype "passive"))
      (node (ref "D227") (pin "2") (pinfunction "K_2") (pintype "passive"))
    )
    (net (code "12") (name "/row4") (class "Default")
      (node (ref "D216") (pin "2") (pinfunction "K_2") (pintype "passive"))
      (node (ref "D218") (pin "2") (pinfunction "K_2") (pintype "passive"))
      (node (ref "D220") (pin "2") (pinfunction "K_2") (pintype "passive"))
      (node (ref "D222") (pin "2") (pinfunction "K_2") (pintype "passive"))
      (node (ref "D224") (pin "2") (pinfunction "K_2") (pintype "passive"))
      (node (ref "D226") (pin "2") (pinfunction "K_2") (pintype "passive"))
      (node (ref "D228") (pin "2") (pinfunction "K_2") (pintype "passive"))
    )
    (net (code "13") (name "/row5") (class "Default")
      (node (ref "D229") (pin "2") (pinfunction "K_2") (pintype "passive"))
      (node (ref "D231") (pin "2") (pinfunction "K_2") (pintype "passive"))
      (node (ref "D233") (pin "2") (pinfunction "K_2") (pintype "passive"))
      (node (ref "D235") (pin "2") (pinfunction "K_2") (pintype "passive"))
      (node (ref "D237") (pin "2") (pinfunction "K_2") (pintype "passive"))
      (node (ref "D239") (pin "2") (pinfunction "K_2") (pintype "passive"))
      (node (ref "D241") (pin "2") (pinfunction "K_2") (pintype "passive"))
    )
    (net (code "14") (name "/row6") (class "Default")
      (node (ref "D230") (pin "2") (pinfunction "K_2") (pintype "passive"))
      (node (ref "D232") (pin "2") (pinfunction "K_2") (pintype "passive"))
      (node (ref "D234") (pin "2") (pinfunction "K_2") (pintype "passive"))
      (node (ref "D236") (pin "2") (pinfunction "K_2") (pintype "passive"))
      (node (ref "D238") (pin "2") (pinfunction "K_2") (pintype "passive"))
      (node (ref "D240") (pin "2") (pinfunction "K_2") (pintype "passive"))
      (node (ref "D242") (pin "2") (pinfunction "K_2") (pintype "passive"))
    )
    (net (code "15") (name "/row7") (class "Default")
      (node (ref "D243") (pin "2") (pinfunction "K_2") (pintype "passive"))
      (node (ref "D245") (pin "2") (pinfunction "K_2") (pintype "passive"))
      (node (ref "D247") (pin "2") (pinfunction "K_2") (pintype "passive"))
      (node (ref "D249") (pin "2") (pinfunction "K_2") (pintype "passive"))
      (node (ref "D251") (pin "2") (pinfunction "K_2") (pintype "passive"))
      (node (ref "D253") (pin "2") (pinfunction "K_2") (pintype "passive"))
      (node (ref "D255") (pin "2") (pinfunction "K_2") (pintype "passive"))
    )
    (net (code "16") (name "/row8") (class "Default")
      (node (ref "D244") (pin "2") (pinfunction "K_2") (pintype "passive"))
      (node (ref "D246") (pin "2") (pinfunction "K_2") (pintype "passive"))
      (node (ref "D248") (pin "2") (pinfunction "K_2") (pintype "passive"))
      (node (ref "D250") (pin "2") (pinfunction "K_2") (pintype "passive"))
      (node (ref "D252") (pin "2") (pinfunction "K_2") (pintype "passive"))
      (node (ref "D254") (pin "2") (pinfunction "K_2") (pintype "passive"))
      (node (ref "D256") (pin "2") (pinfunction "K_2") (pintype "passive"))
    )
    (net (code "17") (name "/row9") (class "Default")
      (node (ref "D257") (pin "2") (pinfunction "K_2") (pintype "passive"))
      (node (ref "D259") (pin "2") (pinfunction "K_2") (pintype "passive"))
      (node (ref "D261") (pin "2") (pinfunction "K_2") (pintype "passive"))
      (node (ref "D263") (pin "2") (pinfunction "K_2") (pintype "passive"))
      (node (ref "D265") (pin "2") (pinfunction "K_2") (pintype "passive"))
      (node (ref "D267") (pin "2") (pinfunction "K_2") (pintype "passive"))
    )
    (net (code "18") (name "/row10") (class "Default")
      (node (ref "D258") (pin "2") (pinfunction "K_2") (pintype "passive"))
      (node (ref "D260") (pin "2") (pinfunction "K_2") (pintype "passive"))
      (node (ref "D262") (pin "2") (pinfunction "K_2") (pintype "passive"))
      (node (ref "D264") (pin "2") (pinfunction "K_2") (pintype "passive"))
      (node (ref "D266") (pin "2") (pinfunction "K_2") (pintype "passive"))
      (node (ref "D270") (pin "2") (pinfunction "K_2") (pintype "passive"))
    )
    (net (code "19") (name "Net-(D201-A)") (class "Default")
      (node (ref "D201") (pin "1") (pinfunction "A_1") (pintype "passive"))
      (node (ref "S201") (pin "1") (pinfunction "1_1") (pintype "passive"))
    )
    (net (code "20") (name "Net-(D202-A)") (class "Default")
      (node (ref "D202") (pin "1") (pinfunction "A_1") (pintype "passive"))
      (node (ref "S202") (pin "1") (pinfunction "1_1") (pintype "passive"))
    )
    (net (code "21") (name "Net-(D203-A)") (class "Default")
      (node (ref "D203") (pin "1") (pinfunction "A_1") (pintype "passive"))
      (node (ref "S203") (pin "1") (pinfunction "1_1") (pintype "passive"))
    )
    (net (code "22") (name "Net-(D204-A)") (class "Default")
      (node (ref "D204") (pin "1") (pinfunction "A_1") (pintype "passive"))
      (node (ref "S204") (pin "1") (pinfunction "1_1") (pintype "passive"))
    )
    (net (code "23") (name "Net-(D205-A)") (class "Default")
      (node (ref "D205") (pin "1") (pinfunction "A_1") (pintype "passive"))
      (node (ref "S205") (pin "1") (pinfunction "1_1") (pintype "passive"))
    )
    (net (code "24") (name "Net-(D206-A)") (class "Default")
      (node (ref "D206") (pin "1") (pinfunction "A_1") (pintype "passive"))
      (node (ref "S206") (pin "1") (pinfunction "1_1") (pintype "passive"))
    )
    (net (code "25") (name "Net-(D207-A)") (class "Default")
      (node (ref "D207") (pin "1") (pinfunction "A_1") (pintype "passive"))
      (node (ref "S207") (pin "1") (pinfunction "1_1") (pintype "passive"))
    )
    (net (code "26") (name "Net-(D208-A)") (class "Default")
      (node (ref "D208") (pin "1") (pinfunction "A_1") (pintype "passive"))
      (node (ref "S208") (pin "1") (pinfunction "1_1") (pintype "passive"))
    )
    (net (code "27") (name "Net-(D209-A)") (class "Default")
      (node (ref "D209") (pin "1") (pinfunction "A_1") (pintype "passive"))
      (node (ref "S209") (pin "1") (pinfunction "1_1") (pintype "passive"))
    )
    (net (code "28") (name "Net-(D210-A)") (class "Default")
      (node (ref "D210") (pin "1") (pinfunction "A_1") (pintype "passive"))
      (node (ref "S210") (pin "1") (pinfunction "1_1") (pintype "passive"))
    )
    (net (code "29") (name "Net-(D211-A)") (class "Default")
      (node (ref "D211") (pin "1") (pinfunction "A_1") (pintype "passive"))
      (node (ref "S211") (pin "1") (pinfunction "1_1") (pintype "passive"))
    )
    (net (code "30") (name "Net-(D212-A)") (class "Default")
      (node (ref "D212") (pin "1") (pinfunction "A_1") (pintype "passive"))
      (node (ref "S212") (pin "1") (pinfunction "1_1") (pintype "passive"))
    )
    (net (code "31") (name "Net-(D213-A)") (class "Default")
      (node (ref "D213") (pin "1") (pinfunction "A_1") (pintype "passive"))
      (node (ref "S213") (pin "1") (pinfunction "1_1") (pintype "passive"))
    )
    (net (code "32") (name "Net-(D214-A)") (class "Default")
      (node (ref "D214") (pin "1") (pinfunction "A_1") (pintype "passive"))
      (node (ref "S214") (pin "1") (pinfunction "1_1") (pintype "passive"))
    )
    (net (code "33") (name "Net-(D215-A)") (class "Default")
      (node (ref "D215") (pin "1") (pinfunction "A_1") (pintype "passive"))
      (node (ref "S215") (pin "1") (pinfunction "1_1") (pintype "passive"))
    )
    (net (code "34") (name "Net-(D216-A)") (class "Default")
      (node (ref "D216") (pin "1") (pinfunction "A_1") (pintype "passive"))
      (node (ref "S216") (pin "1") (pinfunction "1_1") (pintype "passive"))
    )
    (net (code "35") (name "Net-(D217-A)") (class "Default")
      (node (ref "D217") (pin "1") (pinfunction "A_1") (pintype "passive"))
      (node (ref "S217") (pin "1") (pinfunction "1_1") (pintype "passive"))
    )
    (net (code "36") (name "Net-(D218-A)") (class "Default")
      (node (ref "D218") (pin "1") (pinfunction "A_1") (pintype "passive"))
      (node (ref "S218") (pin "1") (pinfunction "1_1") (pintype "passive"))
    )
    (net (code "37") (name "Net-(D219-A)") (class "Default")
      (node (ref "D219") (pin "1") (pinfunction "A_1") (pintype "passive"))
      (node (ref "S219") (pin "1") (pinfunction "1_1") (pintype "passive"))
    )
    (net (code "38") (name "Net-(D220-A)") (class "Default")
      (node (ref "D220") (pin "1") (pinfunction "A_1") (pintype "passive"))
      (node (ref "S220") (pin "1") (pinfunction "1_1") (pintype "passive"))
    )
    (net (code "39") (name "Net-(D221-A)") (class "Default")
      (node (ref "D221") (pin "1") (pinfunction "A_1") (pintype "passive"))
      (node (ref "S221") (pin "1") (pinfunction "1_1") (pintype "passive"))
    )
    (net (code "40") (name "Net-(D222-A)") (class "Default")
      (node (ref "D222") (pin "1") (pinfunction "A_1") (pintype "passive"))
      (node (ref "S222") (pin "1") (pinfunction "1_1") (pintype "passive"))
    )
    (net (code "41") (name "Net-(D223-A)") (class "Default")
      (node (ref "D223") (pin "1") (pinfunction "A_1") (pintype "passive"))
      (node (ref "S223") (pin "1") (pinfunction "1_1") (pintype "passive"))
    )
    (net (code "42") (name "Net-(D224-A)") (class "Default")
      (node (ref "D224") (pin "1") (pinfunction "A_1") (pintype "passive"))
      (node (ref "S224") (pin "1") (pinfunction "1_1") (pintype "passive"))
    )
    (net (code "43") (name "Net-(D225-A)") (class "Default")
      (node (ref "D225") (pin "1") (pinfunction "A_1") (pintype "passive"))
      (node (ref "S225") (pin "1") (pinfunction "1_1") (pintype "passive"))
    )
    (net (code "44") (name "Net-(D226-A)") (class "Default")
      (node (ref "D226") (pin "1") (pinfunction "A_1") (pintype "passive"))
      (node (ref "S226") (pin "1") (pinfunction "1_1") (pintype "passive"))
    )
    (net (code "45") (name "Net-(D227-A)") (class "Default")
      (node (ref "D227") (pin "1") (pinfunction "A_1") (pintype "passive"))
      (node (ref "S227") (pin "1") (pinfunction "1_1") (pintype "passive"))
    )
    (net (code "46") (name "Net-(D228-A)") (class "Default")
      (node (ref "D228") (pin "1") (pinfunction "A_1") (pintype "passive"))
      (node (ref "S228") (pin "2") (pinfunction "2_2") (pintype "passive"))
    )
    (net (code "47") (name "Net-(D229-A)") (class "Default")
      (node (ref "D229") (pin "1") (pinfunction "A_1") (pintype "passive"))
      (node (ref "S229") (pin "1") (pinfunction "1_1") (pintype "passive"))
    )
    (net (code "48") (name "Net-(D230-A)") (class "Default")
      (node (ref "D230") (pin "1") (pinfunction "A_1") (pintype "passive"))
      (node (ref "S230") (pin "1") (pinfunction "1_1") (pintype "passive"))
    )
    (net (code "49") (name "Net-(D231-A)") (class "Default")
      (node (ref "D231") (pin "1") (pinfunction "A_1") (pintype "passive"))
      (node (ref "S231") (pin "1") (pinfunction "1_1") (pintype "passive"))
    )
    (net (code "50") (name "Net-(D232-A)") (class "Default")
      (node (ref "D232") (pin "1") (pinfunction "A_1") (pintype "passive"))
      (node (ref "S232") (pin "1") (pinfunction "1_1") (pintype "passive"))
    )
    (net (code "51") (name "Net-(D233-A)") (class "Default")
      (node (ref "D233") (pin "1") (pinfunction "A_1") (pintype "passive"))
      (node (ref "S233") (pin "1") (pinfunction "1_1") (pintype "passive"))
    )
    (net (code "52") (name "Net-(D234-A)") (class "Default")
      (node (ref "D234") (pin "1") (pinfunction "A_1") (pintype "passive"))
      (node (ref "S234") (pin "1") (pinfunction "1_1") (pintype "passive"))
    )
    (net (code "53") (name "Net-(D235-A)") (class "Default")
      (node (ref "D235") (pin "1") (pinfunction "A_1") (pintype "passive"))
      (node (ref "S235") (pin "1") (pinfunction "1_1") (pintype "passive"))
    )
    (net (code "54") (name "Net-(D236-A)") (class "Default")
      (node (ref "D236") (pin "1") (pinfunction "A_1") (pintype "passive"))
      (node (ref "S236") (pin "1") (pinfunction "1_1") (pintype "passive"))
    )
    (net (code "55") (name "Net-(D237-A)") (class "Default")
      (node (ref "D237") (pin "1") (pinfunction "A_1") (pintype "passive"))
      (node (ref "S237") (pin "1") (pinfunction "1_1") (pintype "passive"))
    )
    (net (code "56") (name "Net-(D238-A)") (class "Default")
      (node (ref "D238") (pin "1") (pinfunction "A_1") (pintype "passive"))
      (node (ref "S238") (pin "1") (pinfunction "1_1") (pintype "passive"))
    )
    (net (code "57") (name "Net-(D239-A)") (class "Default")
      (node (ref "D239") (pin "1") (pinfunction "A_1") (pintype "passive"))
      (node (ref "S239") (pin "1") (pinfunction "1_1") (pintype "passive"))
    )
    (net (code "58") (name "Net-(D240-A)") (class "Default")
      (node (ref "D240") (pin "1") (pinfunction "A_1") (pintype "passive"))
      (node (ref "S240") (pin "1") (pinfunction "1_1") (pintype "passive"))
    )
    (net (code "59") (name "Net-(D241-A)") (class "Default")
      (node (ref "D241") (pin "1") (pinfunction "A_1") (pintype "passive"))
      (node (ref "S241") (pin "1") (pinfunction "1_1") (pintype "passive"))
    )
    (net (code "60") (name "Net-(D242-A)") (class "Default")
      (node (ref "D242") (pin "1") (pinfunction "A_1") (pintype "passive"))
      (node (ref "S242") (pin "1") (pinfunction "1_1") (pintype "passive"))
    )
    (net (code "61") (name "Net-(D243-A)") (class "Default")
      (node (ref "D243") (pin "1") (pinfunction "A_1") (pintype "passive"))
      (node (ref "S243") (pin "1") (pinfunction "1_1") (pintype "passive"))
    )
    (net (code "62") (name "Net-(D244-A)") (class "Default")
      (node (ref "D244") (pin "1") (pinfunction "A_1") (pintype "passive"))
      (node (ref "S244") (pin "1") (pinfunction "1_1") (pintype "passive"))
    )
    (net (code "63") (name "Net-(D245-A)") (class "Default")
      (node (ref "D245") (pin "1") (pinfunction "A_1") (pintype "passive"))
      (node (ref "S245") (pin "1") (pinfunction "1_1") (pintype "passive"))
    )
    (net (code "64") (name "Net-(D246-A)") (class "Default")
      (node (ref "D246") (pin "1") (pinfunction "A_1") (pintype "passive"))
      (node (ref "S246") (pin "1") (pinfunction "1_1") (pintype "passive"))
    )
    (net (code "65") (name "Net-(D247-A)") (class "Default")
      (node (ref "D247") (pin "1") (pinfunction "A_1") (pintype "passive"))
      (node (ref "S247") (pin "1") (pinfunction "1_1") (pintype "passive"))
    )
    (net (code "66") (name "Net-(D248-A)") (class "Default")
      (node (ref "D248") (pin "1") (pinfunction "A_1") (pintype "passive"))
      (node (ref "S248") (pin "1") (pinfunction "1_1") (pintype "passive"))
    )
    (net (code "67") (name "Net-(D249-A)") (class "Default")
      (node (ref "D249") (pin "1") (pinfunction "A_1") (pintype "passive"))
      (node (ref "S249") (pin "1") (pinfunction "1_1") (pintype "passive"))
    )
    (net (code "68") (name "Net-(D250-A)") (class "Default")
      (node (ref "D250") (pin "1") (pinfunction "A_1") (pintype "passive"))
      (node (ref "S250") (pin "1") (pinfunction "1_1") (pintype "passive"))
    )
    (net (code "69") (name "Net-(D251-A)") (class "Default")
      (node (ref "D251") (pin "1") (pinfunction "A_1") (pintype "passive"))
      (node (ref "S251") (pin "1") (pinfunction "1_1") (pintype "passive"))
    )
    (net (code "70") (name "Net-(D252-A)") (class "Default")
      (node (ref "D252") (pin "1") (pinfunction "A_1") (pintype "passive"))
      (node (ref "S252") (pin "1") (pinfunction "1_1") (pintype "passive"))
    )
    (net (code "71") (name "Net-(D253-A)") (class "Default")
      (node (ref "D253") (pin "1") (pinfunction "A_1") (pintype "passive"))
      (node (ref "S253") (pin "1") (pinfunction "1_1") (pintype "passive"))
    )
    (net (code "72") (name "Net-(D254-A)") (class "Default")
      (node (ref "D254") (pin "1") (pinfunction "A_1") (pintype "passive"))
      (node (ref "S254") (pin "1") (pinfunction "1_1") (pintype "passive"))
    )
    (net (code "73") (name "Net-(D255-A)") (class "Default")
      (node (ref "D255") (pin "1") (pinfunction "A_1") (pintype "passive"))
      (node (ref "S255") (pin "1") (pinfunction "1_1") (pintype "passive"))
    )
    (net (code "74") (name "Net-(D256-A)") (class "Default")
      (node (ref "D256") (pin "1") (pinfunction "A_1") (pintype "passive"))
      (node (ref "S256") (pin "1") (pinfunction "1_1") (pintype "passive"))
    )
    (net (code "75") (name "Net-(D257-A)") (class "Default")
      (node (ref "D257") (pin "1") (pinfunction "A_1") (pintype "passive"))
      (node (ref "S257") (pin "1") (pinfunction "1_1") (pintype "passive"))
    )
    (net (code "76") (name "Net-(D258-A)") (class "Default")
      (node (ref "D258") (pin "1") (pinfunction "A_1") (pintype "passive"))
      (node (ref "S258") (pin "1") (pinfunction "1_1") (pintype "passive"))
    )
    (net (code "77") (name "Net-(D259-A)") (class "Default")
      (node (ref "D259") (pin "1") (pinfunction "A_1") (pintype "passive"))
      (node (ref "S259") (pin "1") (pinfunction "1_1") (pintype "passive"))
    )
    (net (code "78") (name "Net-(D260-A)") (class "Default")
      (node (ref "D260") (pin "1") (pinfunction "A_1") (pintype "passive"))
      (node (ref "S260") (pin "1") (pinfunction "1_1") (pintype "passive"))
    )
    (net (code "79") (name "Net-(D261-A)") (class "Default")
      (node (ref "D261") (pin "1") (pinfunction "A_1") (pintype "passive"))
      (node (ref "S261") (pin "2") (pinfunction "2_2") (pintype "passive"))
    )
    (net (code "80") (name "Net-(D262-A)") (class "Default")
      (node (ref "D262") (pin "1") (pinfunction "A_1") (pintype "passive"))
      (node (ref "S262") (pin "1") (pinfunction "1_1") (pintype "passive"))
    )
    (net (code "81") (name "Net-(D263-A)") (class "Default")
      (node (ref "D263") (pin "1") (pinfunction "A_1") (pintype "passive"))
      (node (ref "S263") (pin "1") (pinfunction "1_1") (pintype "passive"))
    )
    (net (code "82") (name "Net-(D264-A)") (class "Default")
      (node (ref "D264") (pin "1") (pinfunction "A_1") (pintype "passive"))
      (node (ref "S264") (pin "2") (pinfunction "2_2") (pintype "passive"))
    )
    (net (code "83") (name "Net-(D265-A)") (class "Default")
      (node (ref "D265") (pin "1") (pinfunction "A_1") (pintype "passive"))
      (node (ref "S265") (pin "1") (pinfunction "1_1") (pintype "passive"))
    )
    (net (code "84") (name "Net-(D266-A)") (class "Default")
      (node (ref "D266") (pin "1") (pinfunction "A_1") (pintype "passive"))
      (node (ref "S266") (pin "1") (pinfunction "1_1") (pintype "passive"))
    )
    (net (code "85") (name "Net-(D267-A)") (class "Default")
      (node (ref "D267") (pin "1") (pinfunction "A_1") (pintype "passive"))
      (node (ref "S267") (pin "1") (pinfunction "1_1") (pintype "passive"))
    )
  )
)
